# Controle-IO.net
KiCad netlist of a schematic drawn in EAGLE
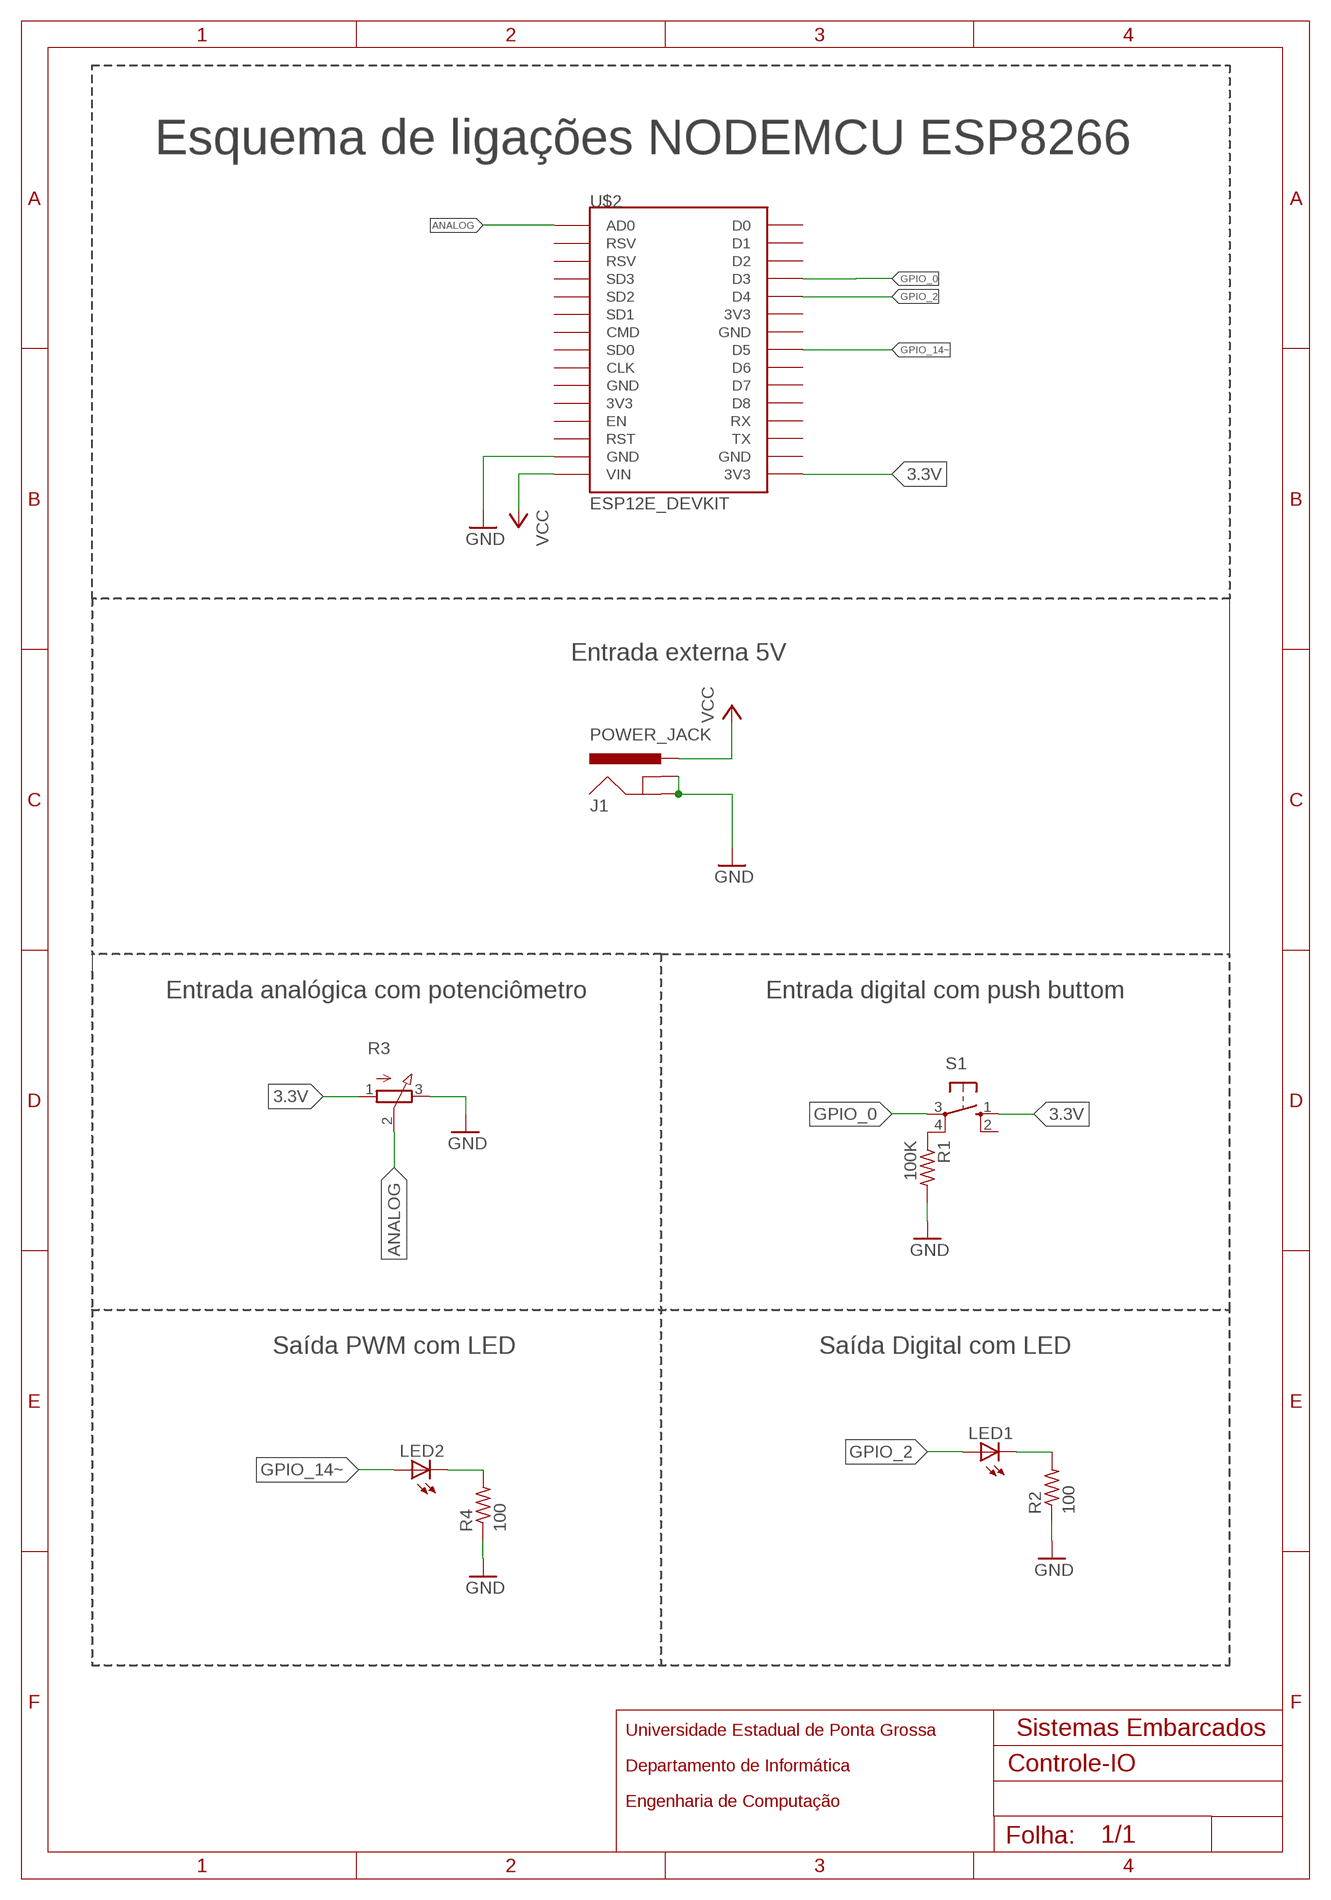
[diagram p0: schematic, sheet 1]

(export (version "E")
  (design (tool "Eeschema 10.0.6"))
  (components
    (comp (ref "J1")
      (value "POWER_JACK")
      (footprint "eagle-import:POWER_JACK_PTH")
      (libsource (lib "eagle-import") (part "POWER_JACK"))
    )
    (comp (ref "LED1")
      (value "LED5MM")
      (footprint "eagle-import:LED5MM")
      (libsource (lib "eagle-import") (part "LED5MM"))
    )
    (comp (ref "LED2")
      (value "LED5MM")
      (footprint "eagle-import:LED5MM")
      (libsource (lib "eagle-import") (part "LED5MM"))
    )
    (comp (ref "R1")
      (value "100K")
      (footprint "eagle-import:0204_7")
      (libsource (lib "eagle-import") (part "R-US_0204/7"))
    )
    (comp (ref "R2")
      (value "100")
      (footprint "eagle-import:0204_7")
      (libsource (lib "eagle-import") (part "R-US_0204/7"))
    )
    (comp (ref "R3")
      (value "3RP/1610N")
      (footprint "eagle-import:3RP_1610N")
      (libsource (lib "eagle-import") (part "3RP/1610N"))
    )
    (comp (ref "R4")
      (value "100")
      (footprint "eagle-import:0204_7")
      (libsource (lib "eagle-import") (part "R-US_0204/7"))
    )
    (comp (ref "S1")
      (value "10-XX")
      (footprint "eagle-import:B3F-10XX")
      (fields (field (name "MPN") "B3F-1000"))
      (libsource (lib "eagle-import") (part "10-XX"))
    )
    (comp (ref "U$2")
      (value "ESP12E_DEVKIT")
      (footprint "eagle-import:ESP12E_DEVKIT")
      (libsource (lib "eagle-import") (part "ESP12E_DEVKIT"))
    )
  )
  (nets
    (net (code "1") (name "/GPIO_14~{}") (class "Default")
      (node (ref "LED2") (pin "A") (pinfunction "A_A") (pintype "passive"))
      (node (ref "U$2") (pin "D5") (pinfunction "D5_D5") (pintype "bidirectional"))
    )
    (net (code "2") (name "3.3V") (class "Default")
      (node (ref "R3") (pin "1") (pinfunction "A_1") (pintype "passive"))
      (node (ref "S1") (pin "1") (pinfunction "S_1") (pintype "passive"))
      (node (ref "U$2") (pin "3V3@2") (pinfunction "3V3_3V3@2") (pintype "bidirectional"))
    )
    (net (code "3") (name "ANALOG") (class "Default")
      (node (ref "R3") (pin "2") (pinfunction "S_2") (pintype "passive"))
      (node (ref "U$2") (pin "AD0") (pinfunction "AD0_AD0") (pintype "bidirectional"))
    )
    (net (code "4") (name "GND") (class "Default")
      (node (ref "J1") (pin "GND") (pinfunction "GND_GND") (pintype "bidirectional"))
      (node (ref "J1") (pin "GNDBREAK") (pinfunction "GNDBREAK_GNDBREAK") (pintype "bidirectional"))
      (node (ref "R1") (pin "2") (pinfunction "2_2") (pintype "passive"))
      (node (ref "R2") (pin "1") (pinfunction "1_1") (pintype "passive"))
      (node (ref "R3") (pin "3") (pinfunction "E_3") (pintype "passive"))
      (node (ref "R4") (pin "1") (pinfunction "1_1") (pintype "passive"))
      (node (ref "U$2") (pin "GND@1") (pinfunction "GND_GND@1") (pintype "bidirectional"))
    )
    (net (code "5") (name "GPIO_0") (class "Default")
      (node (ref "S1") (pin "3") (pinfunction "P_3") (pintype "passive"))
      (node (ref "U$2") (pin "D3") (pinfunction "D3_D3") (pintype "bidirectional"))
    )
    (net (code "6") (name "GPIO_2") (class "Default")
      (node (ref "LED1") (pin "A") (pinfunction "A_A") (pintype "passive"))
      (node (ref "U$2") (pin "D4") (pinfunction "D4_D4") (pintype "bidirectional"))
    )
    (net (code "7") (name "Net-(LED1-C)") (class "Default")
      (node (ref "LED1") (pin "K") (pinfunction "C_K") (pintype "passive"))
      (node (ref "R2") (pin "2") (pinfunction "2_2") (pintype "passive"))
    )
    (net (code "8") (name "Net-(LED2-C)") (class "Default")
      (node (ref "LED2") (pin "K") (pinfunction "C_K") (pintype "passive"))
      (node (ref "R4") (pin "2") (pinfunction "2_2") (pintype "passive"))
    )
    (net (code "9") (name "Net-(S1-P1)") (class "Default")
      (node (ref "R1") (pin "1") (pinfunction "1_1") (pintype "passive"))
      (node (ref "S1") (pin "4") (pinfunction "P1_4") (pintype "passive"))
    )
    (net (code "10") (name "VCC") (class "Default")
      (node (ref "J1") (pin "PWR") (pinfunction "PWR_PWR") (pintype "bidirectional"))
      (node (ref "U$2") (pin "VIN") (pinfunction "VIN_VIN") (pintype "bidirectional"))
    )
    (net (code "11") (name "unconnected-(S1-S1-Pad2)") (class "Default")
      (node (ref "S1") (pin "2") (pinfunction "S1_2") (pintype "passive"))
    )
    (net (code "12") (name "unconnected-(U$2-3V3-Pad3V3@0)") (class "Default")
      (node (ref "U$2") (pin "3V3@0") (pinfunction "3V3_3V3@0") (pintype "bidirectional"))
    )
    (net (code "13") (name "unconnected-(U$2-3V3-Pad3V3@1)") (class "Default")
      (node (ref "U$2") (pin "3V3@1") (pinfunction "3V3_3V3@1") (pintype "bidirectional"))
    )
    (net (code "14") (name "unconnected-(U$2-GND-PadGND@0)") (class "Default")
      (node (ref "U$2") (pin "GND@0") (pinfunction "GND_GND@0") (pintype "bidirectional"))
    )
    (net (code "15") (name "unconnected-(U$2-GND-PadGND@2)") (class "Default")
      (node (ref "U$2") (pin "GND@2") (pinfunction "GND_GND@2") (pintype "bidirectional"))
    )
    (net (code "16") (name "unconnected-(U$2-GND-PadGND@3)") (class "Default")
      (node (ref "U$2") (pin "GND@3") (pinfunction "GND_GND@3") (pintype "bidirectional"))
    )
    (net (code "17") (name "unconnected-(U$2-PadCLK)") (class "Default")
      (node (ref "U$2") (pin "CLK") (pinfunction "CLK_CLK") (pintype "bidirectional"))
    )
    (net (code "18") (name "unconnected-(U$2-PadCMD)") (class "Default")
      (node (ref "U$2") (pin "CMD") (pinfunction "CMD_CMD") (pintype "bidirectional"))
    )
    (net (code "19") (name "unconnected-(U$2-PadD0)") (class "Default")
      (node (ref "U$2") (pin "D0") (pinfunction "D0_D0") (pintype "bidirectional"))
    )
    (net (code "20") (name "unconnected-(U$2-PadD1)") (class "Default")
      (node (ref "U$2") (pin "D1") (pinfunction "D1_D1") (pintype "bidirectional"))
    )
    (net (code "21") (name "unconnected-(U$2-PadD2)") (class "Default")
      (node (ref "U$2") (pin "D2") (pinfunction "D2_D2") (pintype "bidirectional"))
    )
    (net (code "22") (name "unconnected-(U$2-PadD6)") (class "Default")
      (node (ref "U$2") (pin "D6") (pinfunction "D6_D6") (pintype "bidirectional"))
    )
    (net (code "23") (name "unconnected-(U$2-PadD7)") (class "Default")
      (node (ref "U$2") (pin "D7") (pinfunction "D7_D7") (pintype "bidirectional"))
    )
    (net (code "24") (name "unconnected-(U$2-PadD8)") (class "Default")
      (node (ref "U$2") (pin "D8") (pinfunction "D8_D8") (pintype "bidirectional"))
    )
    (net (code "25") (name "unconnected-(U$2-PadEN)") (class "Default")
      (node (ref "U$2") (pin "EN") (pinfunction "EN_EN") (pintype "bidirectional"))
    )
    (net (code "26") (name "unconnected-(U$2-PadRST)") (class "Default")
      (node (ref "U$2") (pin "RST") (pinfunction "RST_RST") (pintype "bidirectional"))
    )
    (net (code "27") (name "unconnected-(U$2-PadRX)") (class "Default")
      (node (ref "U$2") (pin "RX") (pinfunction "RX_RX") (pintype "bidirectional"))
    )
    (net (code "28") (name "unconnected-(U$2-PadSD0)") (class "Default")
      (node (ref "U$2") (pin "SD0") (pinfunction "SD0_SD0") (pintype "bidirectional"))
    )
    (net (code "29") (name "unconnected-(U$2-PadSD1)") (class "Default")
      (node (ref "U$2") (pin "SD1") (pinfunction "SD1_SD1") (pintype "bidirectional"))
    )
    (net (code "30") (name "unconnected-(U$2-PadSD2)") (class "Default")
      (node (ref "U$2") (pin "SD2") (pinfunction "SD2_SD2") (pintype "bidirectional"))
    )
    (net (code "31") (name "unconnected-(U$2-PadSD3)") (class "Default")
      (node (ref "U$2") (pin "SD3") (pinfunction "SD3_SD3") (pintype "bidirectional"))
    )
    (net (code "32") (name "unconnected-(U$2-PadTX)") (class "Default")
      (node (ref "U$2") (pin "TX") (pinfunction "TX_TX") (pintype "bidirectional"))
    )
    (net (code "33") (name "unconnected-(U$2-RSV-PadRSV@0)") (class "Default")
      (node (ref "U$2") (pin "RSV@0") (pinfunction "RSV_RSV@0") (pintype "bidirectional"))
    )
    (net (code "34") (name "unconnected-(U$2-RSV-PadRSV@1)") (class "Default")
      (node (ref "U$2") (pin "RSV@1") (pinfunction "RSV_RSV@1") (pintype "bidirectional"))
    )
  )
)
